# Movim.net
KiCad netlist of a schematic drawn in EAGLE
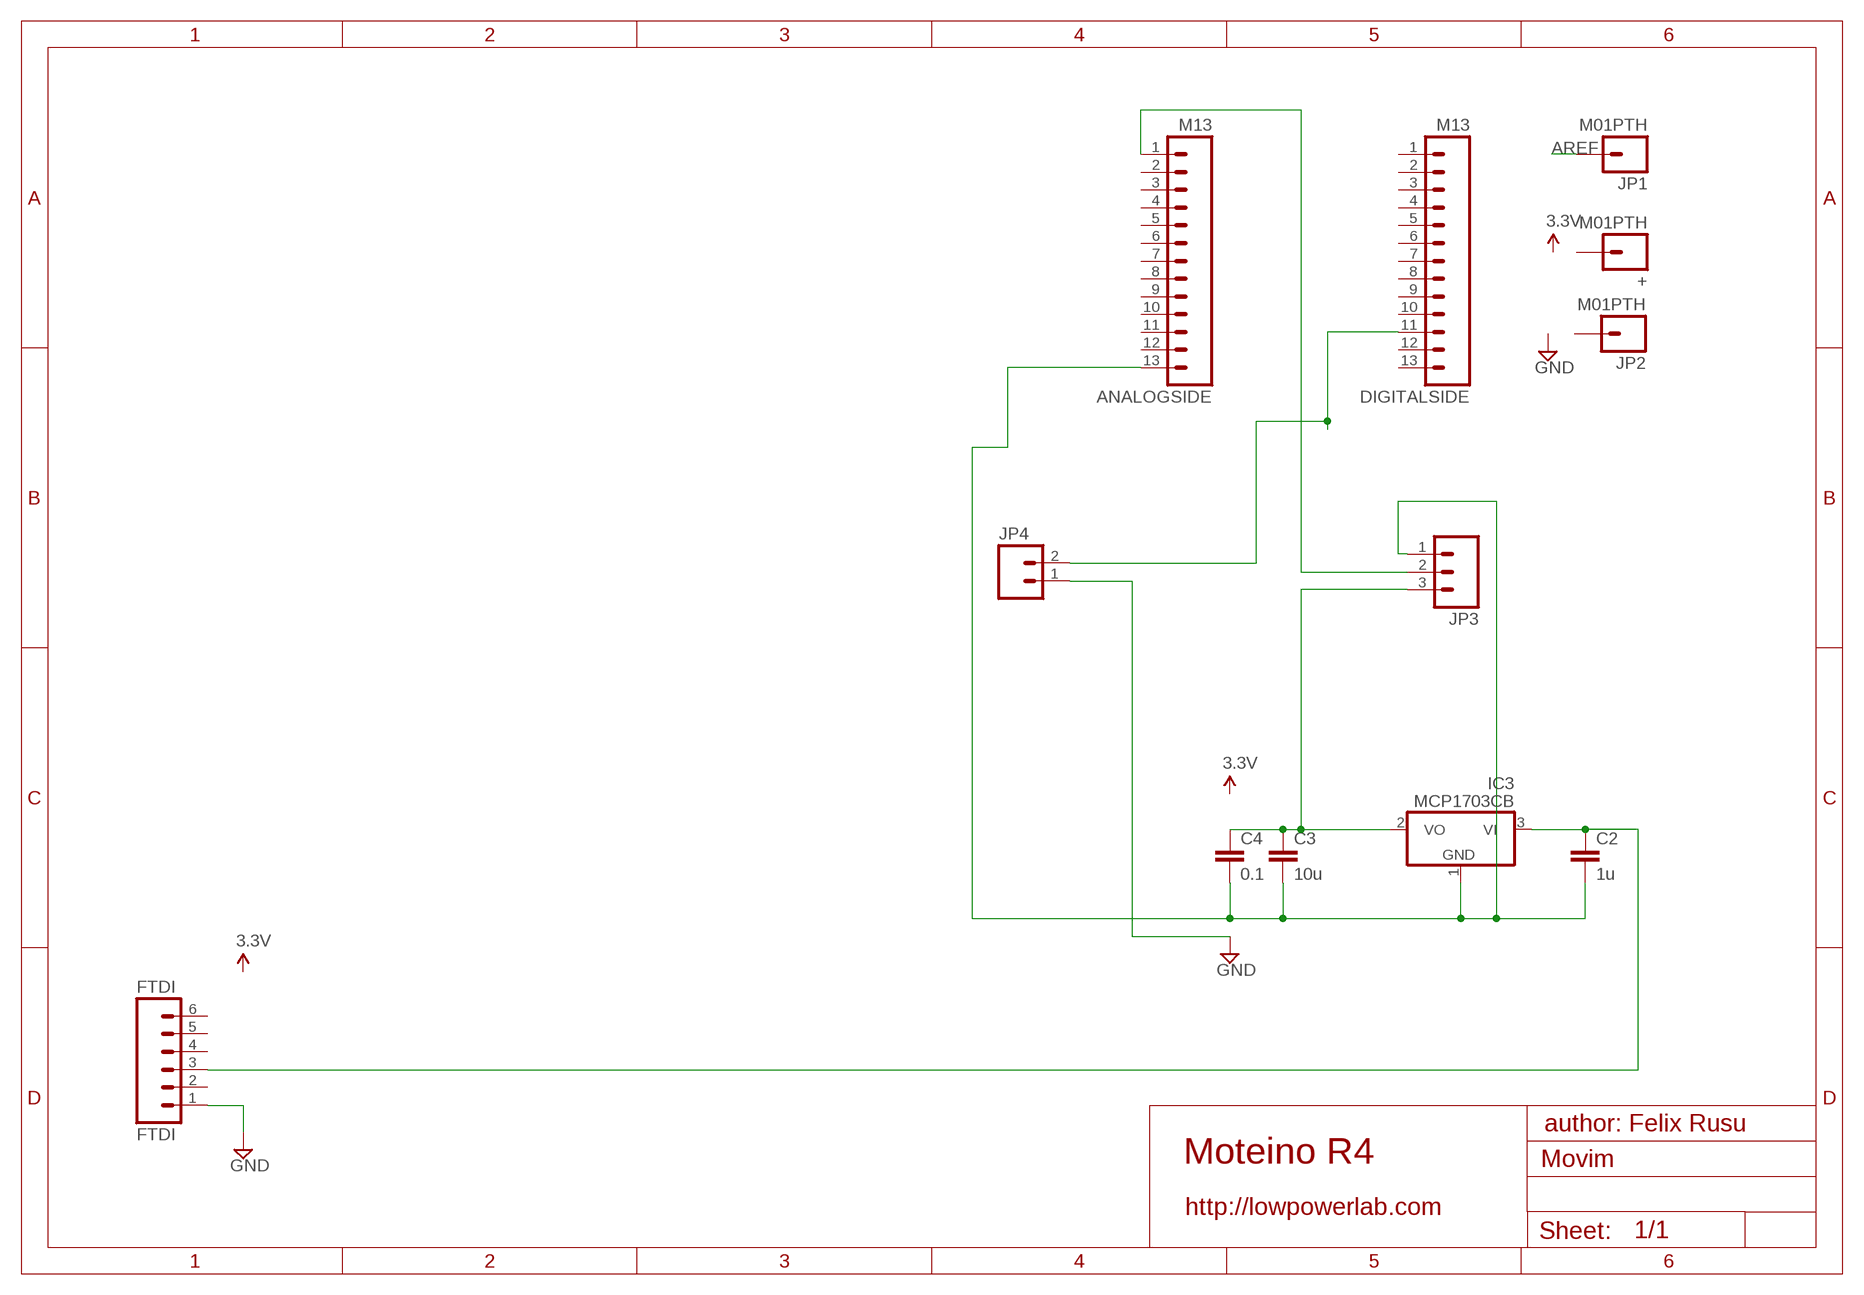
[diagram p0: schematic, sheet 1]

(export (version "E")
  (design (tool "Eeschema 10.0.6"))
  (components
    (comp (ref "+")
      (value "M01PTH")
      (footprint "eagle-import:1X01")
      (libsource (lib "eagle-import") (part "M01PTH"))
    )
    (comp (ref "ANALOGSIDE")
      (value "M13")
      (footprint "eagle-import:1X13")
      (libsource (lib "eagle-import") (part "M13"))
    )
    (comp (ref "C2")
      (value "1u")
      (footprint "eagle-import:0603-CAP")
      (libsource (lib "eagle-import") (part "CAP0603-CAP"))
    )
    (comp (ref "C3")
      (value "10u")
      (footprint "eagle-import:0805-CAP")
      (libsource (lib "eagle-import") (part "CAP0805-CAP"))
    )
    (comp (ref "C4")
      (value "0.1")
      (footprint "eagle-import:0603-CAP")
      (libsource (lib "eagle-import") (part "CAP0603-CAP"))
    )
    (comp (ref "DIGITALSIDE")
      (value "M13")
      (footprint "eagle-import:1X13")
      (libsource (lib "eagle-import") (part "M13"))
    )
    (comp (ref "FTDI")
      (value "FTDI")
      (footprint "eagle-import:1X06")
      (libsource (lib "eagle-import") (part "M06SIP"))
    )
    (comp (ref "IC3")
      (value "MCP1703CB")
      (footprint "eagle-import:SOT23")
      (libsource (lib "eagle-import") (part "MCP1703CB"))
    )
    (comp (ref "JP1")
      (value "M01PTH")
      (footprint "eagle-import:1X01")
      (libsource (lib "eagle-import") (part "M01PTH"))
    )
    (comp (ref "JP2")
      (value "M01PTH")
      (footprint "eagle-import:1X01")
      (libsource (lib "eagle-import") (part "M01PTH"))
    )
    (comp (ref "JP3")
      (value "M03PTH")
      (footprint "eagle-import:1X03")
      (libsource (lib "eagle-import") (part "M03PTH"))
    )
    (comp (ref "JP4")
      (value "M02PTH")
      (footprint "eagle-import:1X02")
      (libsource (lib "eagle-import") (part "M02PTH"))
    )
  )
  (nets
    (net (code "1") (name "/AREF") (class "Default")
      (node (ref "JP1") (pin "1") (pinfunction "1_1") (pintype "passive"))
    )
    (net (code "3") (name "GND") (class "Default")
      (node (ref "FTDI") (pin "1") (pinfunction "1_1") (pintype "passive"))
      (node (ref "JP4") (pin "1") (pinfunction "1_1") (pintype "passive"))
    )
    (net (code "4") (name "Net-(ANALOGSIDE-Pad1)") (class "Default")
      (node (ref "ANALOGSIDE") (pin "1") (pinfunction "1_1") (pintype "passive"))
      (node (ref "JP3") (pin "2") (pinfunction "2_2") (pintype "passive"))
    )
    (net (code "5") (name "Net-(DIGITALSIDE-Pad11)") (class "Default")
      (node (ref "DIGITALSIDE") (pin "11") (pinfunction "11_11") (pintype "passive"))
      (node (ref "JP4") (pin "2") (pinfunction "2_2") (pintype "passive"))
    )
    (net (code "6") (name "Net-(IC3-GND)") (class "Default")
      (node (ref "ANALOGSIDE") (pin "13") (pinfunction "13_13") (pintype "passive"))
      (node (ref "C2") (pin "2") (pinfunction "2_2") (pintype "passive"))
      (node (ref "C3") (pin "2") (pinfunction "2_2") (pintype "passive"))
      (node (ref "C4") (pin "2") (pinfunction "2_2") (pintype "passive"))
      (node (ref "IC3") (pin "1") (pinfunction "GND_1") (pintype "passive"))
      (node (ref "JP3") (pin "1") (pinfunction "1_1") (pintype "passive"))
    )
    (net (code "7") (name "Net-(IC3-VI)") (class "Default")
      (node (ref "C2") (pin "1") (pinfunction "1_1") (pintype "passive"))
      (node (ref "FTDI") (pin "3") (pinfunction "3_3") (pintype "passive"))
      (node (ref "IC3") (pin "3") (pinfunction "VI_3") (pintype "input"))
    )
    (net (code "8") (name "Net-(IC3-VO)") (class "Default")
      (node (ref "C3") (pin "1") (pinfunction "1_1") (pintype "passive"))
      (node (ref "C4") (pin "1") (pinfunction "1_1") (pintype "passive"))
      (node (ref "IC3") (pin "2") (pinfunction "VO_2") (pintype "passive"))
      (node (ref "JP3") (pin "3") (pinfunction "3_3") (pintype "passive"))
    )
    (net (code "9") (name "unconnected-(+-Pad1)") (class "Default")
      (node (ref "+") (pin "1") (pinfunction "1_1") (pintype "passive"))
    )
    (net (code "10") (name "unconnected-(ANALOGSIDE-Pad2)") (class "Default")
      (node (ref "ANALOGSIDE") (pin "2") (pinfunction "2_2") (pintype "passive"))
    )
    (net (code "11") (name "unconnected-(ANALOGSIDE-Pad3)") (class "Default")
      (node (ref "ANALOGSIDE") (pin "3") (pinfunction "3_3") (pintype "passive"))
    )
    (net (code "12") (name "unconnected-(ANALOGSIDE-Pad4)") (class "Default")
      (node (ref "ANALOGSIDE") (pin "4") (pinfunction "4_4") (pintype "passive"))
    )
    (net (code "13") (name "unconnected-(ANALOGSIDE-Pad5)") (class "Default")
      (node (ref "ANALOGSIDE") (pin "5") (pinfunction "5_5") (pintype "passive"))
    )
    (net (code "14") (name "unconnected-(ANALOGSIDE-Pad6)") (class "Default")
      (node (ref "ANALOGSIDE") (pin "6") (pinfunction "6_6") (pintype "passive"))
    )
    (net (code "15") (name "unconnected-(ANALOGSIDE-Pad7)") (class "Default")
      (node (ref "ANALOGSIDE") (pin "7") (pinfunction "7_7") (pintype "passive"))
    )
    (net (code "16") (name "unconnected-(ANALOGSIDE-Pad8)") (class "Default")
      (node (ref "ANALOGSIDE") (pin "8") (pinfunction "8_8") (pintype "passive"))
    )
    (net (code "17") (name "unconnected-(ANALOGSIDE-Pad9)") (class "Default")
      (node (ref "ANALOGSIDE") (pin "9") (pinfunction "9_9") (pintype "passive"))
    )
    (net (code "18") (name "unconnected-(ANALOGSIDE-Pad10)") (class "Default")
      (node (ref "ANALOGSIDE") (pin "10") (pinfunction "10_10") (pintype "passive"))
    )
    (net (code "19") (name "unconnected-(ANALOGSIDE-Pad11)") (class "Default")
      (node (ref "ANALOGSIDE") (pin "11") (pinfunction "11_11") (pintype "passive"))
    )
    (net (code "20") (name "unconnected-(ANALOGSIDE-Pad12)") (class "Default")
      (node (ref "ANALOGSIDE") (pin "12") (pinfunction "12_12") (pintype "passive"))
    )
    (net (code "21") (name "unconnected-(DIGITALSIDE-Pad1)") (class "Default")
      (node (ref "DIGITALSIDE") (pin "1") (pinfunction "1_1") (pintype "passive"))
    )
    (net (code "22") (name "unconnected-(DIGITALSIDE-Pad2)") (class "Default")
      (node (ref "DIGITALSIDE") (pin "2") (pinfunction "2_2") (pintype "passive"))
    )
    (net (code "23") (name "unconnected-(DIGITALSIDE-Pad3)") (class "Default")
      (node (ref "DIGITALSIDE") (pin "3") (pinfunction "3_3") (pintype "passive"))
    )
    (net (code "24") (name "unconnected-(DIGITALSIDE-Pad4)") (class "Default")
      (node (ref "DIGITALSIDE") (pin "4") (pinfunction "4_4") (pintype "passive"))
    )
    (net (code "25") (name "unconnected-(DIGITALSIDE-Pad5)") (class "Default")
      (node (ref "DIGITALSIDE") (pin "5") (pinfunction "5_5") (pintype "passive"))
    )
    (net (code "26") (name "unconnected-(DIGITALSIDE-Pad6)") (class "Default")
      (node (ref "DIGITALSIDE") (pin "6") (pinfunction "6_6") (pintype "passive"))
    )
    (net (code "27") (name "unconnected-(DIGITALSIDE-Pad7)") (class "Default")
      (node (ref "DIGITALSIDE") (pin "7") (pinfunction "7_7") (pintype "passive"))
    )
    (net (code "28") (name "unconnected-(DIGITALSIDE-Pad8)") (class "Default")
      (node (ref "DIGITALSIDE") (pin "8") (pinfunction "8_8") (pintype "passive"))
    )
    (net (code "29") (name "unconnected-(DIGITALSIDE-Pad9)") (class "Default")
      (node (ref "DIGITALSIDE") (pin "9") (pinfunction "9_9") (pintype "passive"))
    )
    (net (code "30") (name "unconnected-(DIGITALSIDE-Pad10)") (class "Default")
      (node (ref "DIGITALSIDE") (pin "10") (pinfunction "10_10") (pintype "passive"))
    )
    (net (code "31") (name "unconnected-(DIGITALSIDE-Pad12)") (class "Default")
      (node (ref "DIGITALSIDE") (pin "12") (pinfunction "12_12") (pintype "passive"))
    )
    (net (code "32") (name "unconnected-(DIGITALSIDE-Pad13)") (class "Default")
      (node (ref "DIGITALSIDE") (pin "13") (pinfunction "13_13") (pintype "passive"))
    )
    (net (code "33") (name "unconnected-(FTDI-Pad2)") (class "Default")
      (node (ref "FTDI") (pin "2") (pinfunction "2_2") (pintype "passive"))
    )
    (net (code "34") (name "unconnected-(FTDI-Pad4)") (class "Default")
      (node (ref "FTDI") (pin "4") (pinfunction "4_4") (pintype "passive"))
    )
    (net (code "35") (name "unconnected-(FTDI-Pad5)") (class "Default")
      (node (ref "FTDI") (pin "5") (pinfunction "5_5") (pintype "passive"))
    )
    (net (code "36") (name "unconnected-(FTDI-Pad6)") (class "Default")
      (node (ref "FTDI") (pin "6") (pinfunction "6_6") (pintype "passive"))
    )
    (net (code "37") (name "unconnected-(JP2-Pad1)") (class "Default")
      (node (ref "JP2") (pin "1") (pinfunction "1_1") (pintype "passive"))
    )
  )
)
